# Neato_Laser_USB.net
KiCad netlist of a schematic drawn in EAGLE
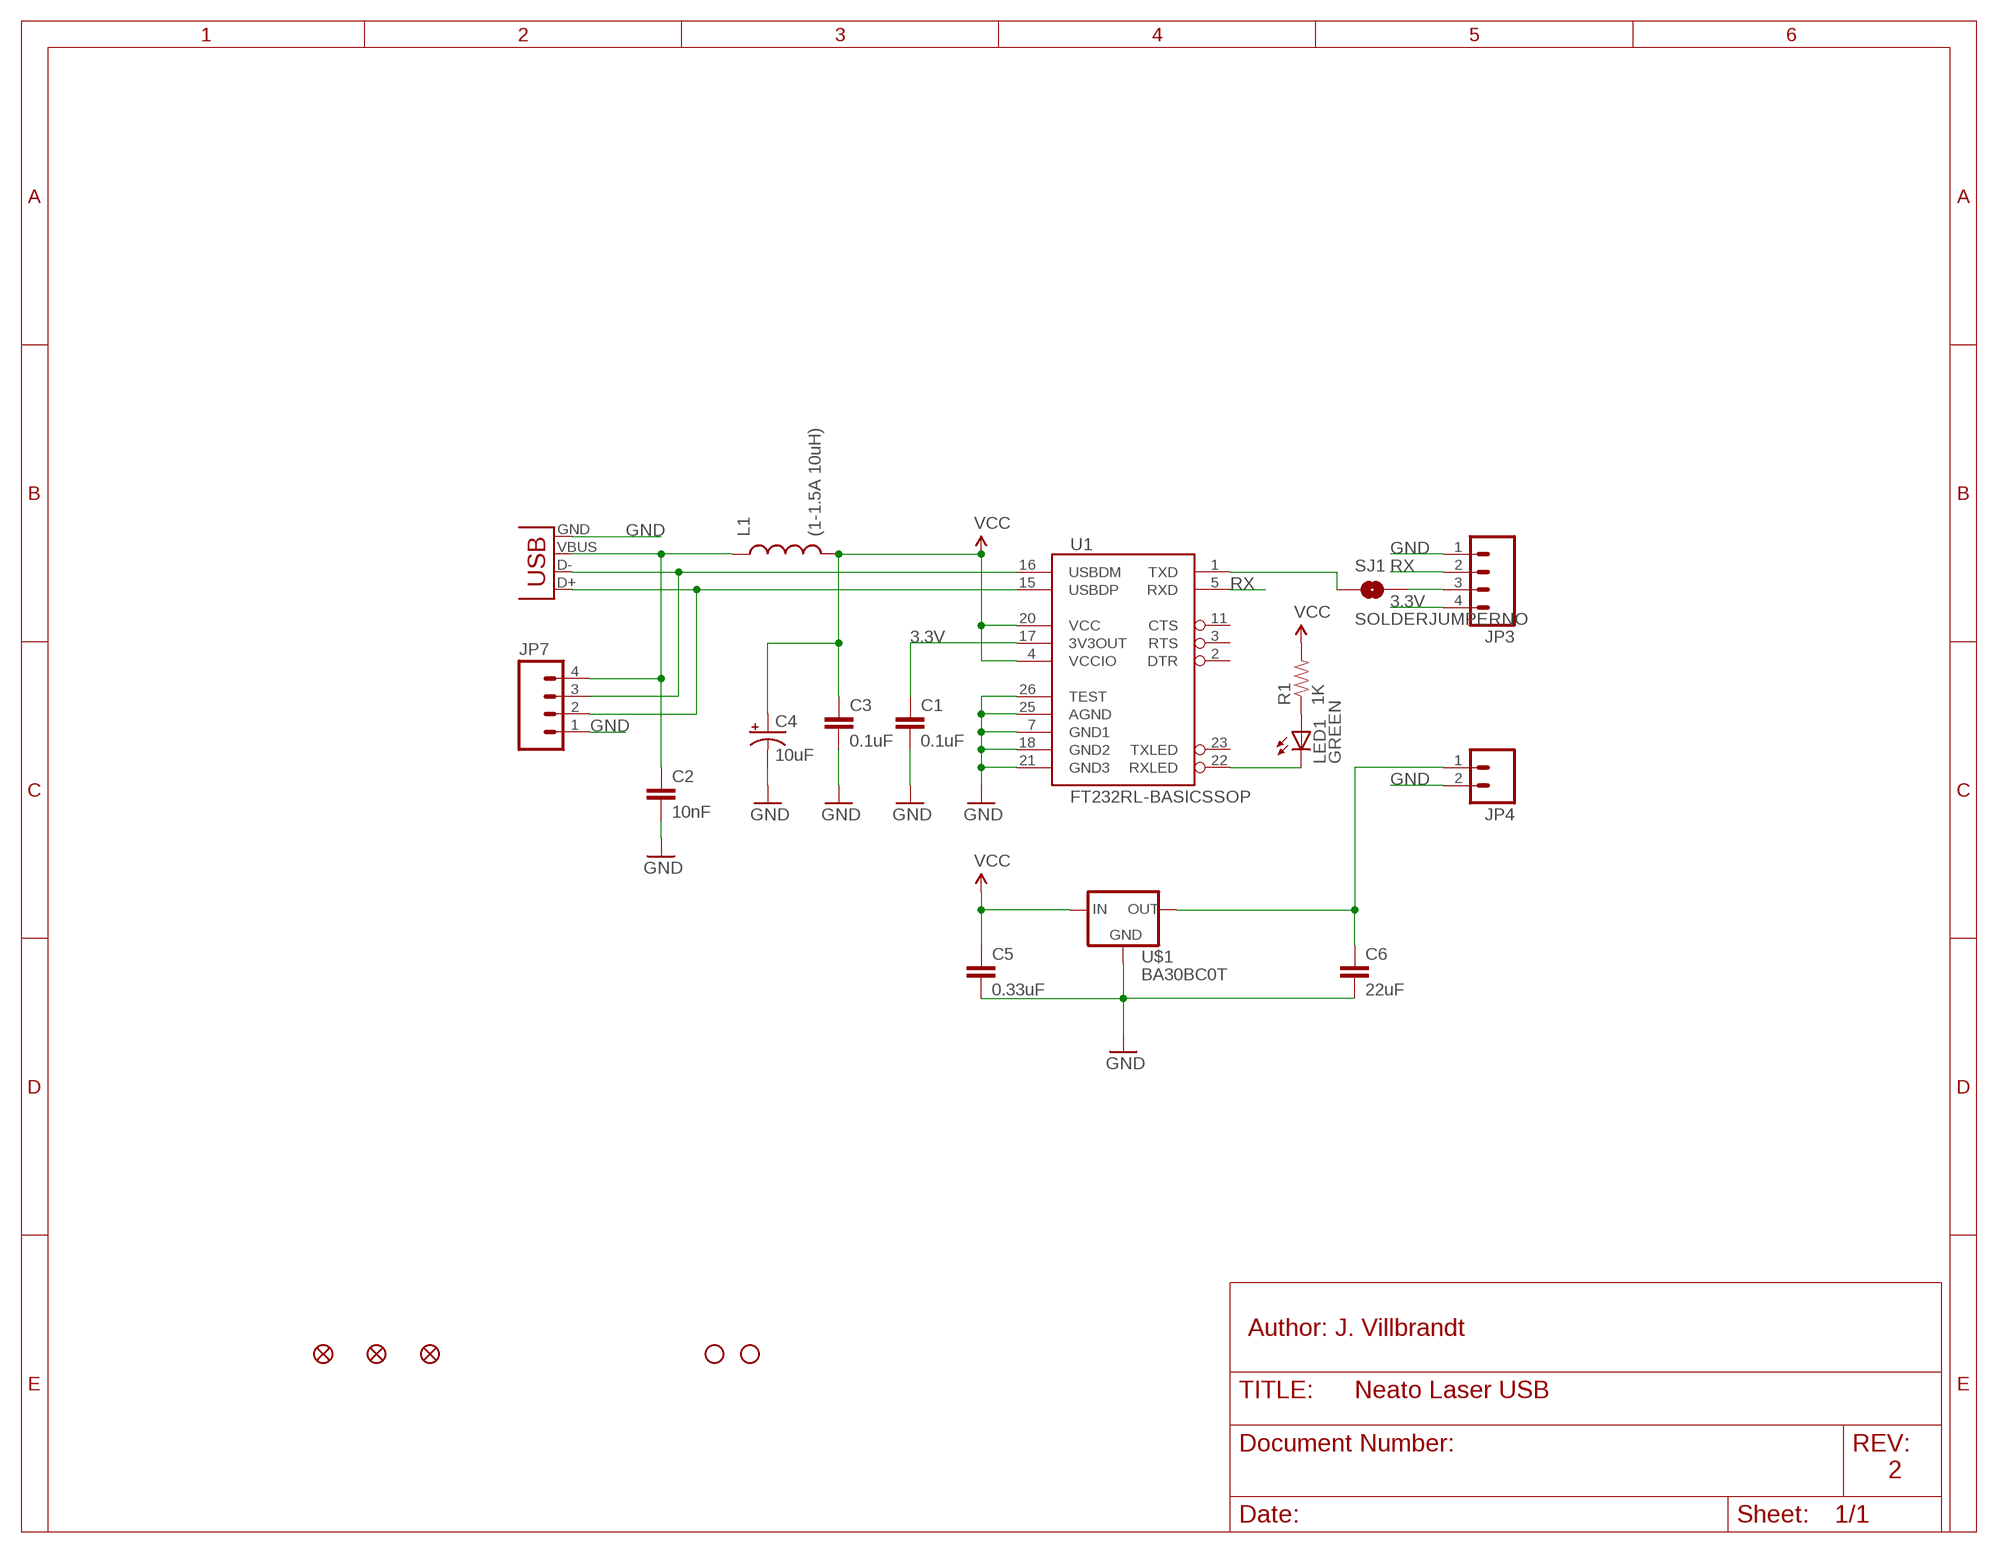
[diagram p0: schematic, sheet 1]

(export (version "E")
  (design (tool "Eeschema 10.0.6"))
  (components
    (comp (ref "C1")
      (value "0.1uF")
      (footprint "eagle-import:0603-CAP")
      (libsource (lib "eagle-import") (part "CAP0603-CAP"))
    )
    (comp (ref "C2")
      (value "10nF")
      (footprint "eagle-import:0603-CAP")
      (libsource (lib "eagle-import") (part "CAP0603-CAP"))
    )
    (comp (ref "C3")
      (value "0.1uF")
      (footprint "eagle-import:0603-CAP")
      (libsource (lib "eagle-import") (part "CAP0603-CAP"))
    )
    (comp (ref "C4")
      (value "10uF")
      (footprint "eagle-import:EIA3216")
      (libsource (lib "eagle-import") (part "CAP_POL1206"))
    )
    (comp (ref "C5")
      (value "0.33uF")
      (footprint "eagle-import:0603-CAP")
      (libsource (lib "eagle-import") (part "CAP0603-CAP"))
    )
    (comp (ref "C6")
      (value "22uF")
      (footprint "eagle-import:0603-CAP")
      (libsource (lib "eagle-import") (part "CAP0603-CAP"))
    )
    (comp (ref "JP1")
      (value "STAND-OFF")
      (footprint "eagle-import:STAND-OFF")
      (libsource (lib "eagle-import") (part "STAND-OFF"))
    )
    (comp (ref "JP2")
      (value "STAND-OFF")
      (footprint "eagle-import:STAND-OFF")
      (libsource (lib "eagle-import") (part "STAND-OFF"))
    )
    (comp (ref "JP3")
      (value "M04JST-PTH")
      (footprint "eagle-import:JST-4-PTH")
      (libsource (lib "eagle-import") (part "M04JST-PTH"))
    )
    (comp (ref "JP4")
      (value "M02JST-PTH-2")
      (footprint "eagle-import:JST-2-PTH")
      (libsource (lib "eagle-import") (part "M02JST-PTH-2"))
    )
    (comp (ref "JP5")
      (value "FIDUCIAL1X2.5")
      (footprint "eagle-import:FIDUCIAL-1X2.5")
      (libsource (lib "eagle-import") (part "FIDUCIAL1X2.5"))
    )
    (comp (ref "JP6")
      (value "FIDUCIAL1X2.5")
      (footprint "eagle-import:FIDUCIAL-1X2.5")
      (libsource (lib "eagle-import") (part "FIDUCIAL1X2.5"))
    )
    (comp (ref "JP7")
      (value "M04PTH")
      (footprint "eagle-import:1X04")
      (libsource (lib "eagle-import") (part "M04PTH"))
    )
    (comp (ref "JP8")
      (value "FIDUCIAL1X2.5")
      (footprint "eagle-import:FIDUCIAL-1X2.5")
      (libsource (lib "eagle-import") (part "FIDUCIAL1X2.5"))
    )
    (comp (ref "L1")
      (value "(1-1.5A 10uH)")
      (footprint "eagle-import:0603")
      (libsource (lib "eagle-import") (part "INDUCTOR0603"))
    )
    (comp (ref "LED1")
      (value "GREEN")
      (footprint "eagle-import:LED-0603")
      (libsource (lib "eagle-import") (part "LED0603"))
    )
    (comp (ref "R1")
      (value "1K")
      (footprint "eagle-import:0402-RES")
      (libsource (lib "eagle-import") (part "RESISTOR0402-RES"))
    )
    (comp (ref "SJ1")
      (value "SOLDERJUMPERNO")
      (footprint "eagle-import:SJ_2S-NO")
      (libsource (lib "eagle-import") (part "SOLDERJUMPERNO"))
    )
    (comp (ref "U$1")
      (value "BA30BC0T")
      (footprint "eagle-import:78XXL")
      (libsource (lib "eagle-import") (part "BA15BC0WT"))
    )
    (comp (ref "U1")
      (value "FT232RL-BASICSSOP")
      (footprint "eagle-import:SSOP28DB")
      (libsource (lib "eagle-import") (part "FT232RL-BASICSSOP"))
    )
    (comp (ref "X1")
      (value "USBSMD")
      (footprint "eagle-import:USB-MINIB")
      (libsource (lib "eagle-import") (part "USBSMD"))
    )
  )
  (nets
    (net (code "1") (name "/3.3V") (class "Default")
      (node (ref "C1") (pin "1") (pinfunction "1_1") (pintype "passive"))
      (node (ref "JP3") (pin "4") (pinfunction "4_4") (pintype "passive"))
      (node (ref "U1") (pin "17") (pinfunction "3V3OUT_17") (pintype "output"))
    )
    (net (code "2") (name "/RX") (class "Default")
      (node (ref "JP3") (pin "2") (pinfunction "2_2") (pintype "passive"))
      (node (ref "U1") (pin "5") (pinfunction "RXD_5") (pintype "input"))
    )
    (net (code "3") (name "GND") (class "Default")
      (node (ref "C1") (pin "2") (pinfunction "2_2") (pintype "passive"))
      (node (ref "C2") (pin "2") (pinfunction "2_2") (pintype "passive"))
      (node (ref "C3") (pin "2") (pinfunction "2_2") (pintype "passive"))
      (node (ref "C4") (pin "C") (pinfunction "-_C") (pintype "passive"))
      (node (ref "C5") (pin "2") (pinfunction "2_2") (pintype "passive"))
      (node (ref "C6") (pin "2") (pinfunction "2_2") (pintype "passive"))
      (node (ref "JP3") (pin "1") (pinfunction "1_1") (pintype "passive"))
      (node (ref "JP4") (pin "2") (pinfunction "2_2") (pintype "passive"))
      (node (ref "JP7") (pin "1") (pinfunction "1_1") (pintype "passive"))
      (node (ref "U$1") (pin "GND") (pinfunction "GND_GND") (pintype "input"))
      (node (ref "U1") (pin "18") (pinfunction "GND2_18") (pintype "power_in"))
      (node (ref "U1") (pin "21") (pinfunction "GND3_21") (pintype "power_in"))
      (node (ref "U1") (pin "25") (pinfunction "AGND_25") (pintype "power_in"))
      (node (ref "U1") (pin "26") (pinfunction "TEST_26") (pintype "input"))
      (node (ref "U1") (pin "7") (pinfunction "GND1_7") (pintype "power_in"))
      (node (ref "X1") (pin "GND") (pinfunction "GND_GND") (pintype "bidirectional"))
    )
    (net (code "4") (name "Net-(C2-Pad1)") (class "Default")
      (node (ref "C2") (pin "1") (pinfunction "1_1") (pintype "passive"))
      (node (ref "JP7") (pin "4") (pinfunction "4_4") (pintype "passive"))
      (node (ref "L1") (pin "1") (pinfunction "1_1") (pintype "passive"))
      (node (ref "X1") (pin "VBUS") (pinfunction "VBUS_VBUS") (pintype "bidirectional"))
    )
    (net (code "5") (name "Net-(C6-Pad1)") (class "Default")
      (node (ref "C6") (pin "1") (pinfunction "1_1") (pintype "passive"))
      (node (ref "JP4") (pin "1") (pinfunction "1_1") (pintype "passive"))
      (node (ref "U$1") (pin "OUT") (pinfunction "OUT_OUT") (pintype "output"))
    )
    (net (code "6") (name "Net-(JP3-Pad3)") (class "Default")
      (node (ref "JP3") (pin "3") (pinfunction "3_3") (pintype "passive"))
      (node (ref "SJ1") (pin "2") (pinfunction "2_2") (pintype "passive"))
    )
    (net (code "7") (name "Net-(LED1-PadA)") (class "Default")
      (node (ref "LED1") (pin "A") (pinfunction "A_A") (pintype "passive"))
      (node (ref "R1") (pin "1") (pinfunction "1_1") (pintype "passive"))
    )
    (net (code "8") (name "Net-(U1-RXLED)") (class "Default")
      (node (ref "LED1") (pin "C") (pinfunction "C_C") (pintype "passive"))
      (node (ref "U1") (pin "22") (pinfunction "RXLED_22") (pintype "bidirectional"))
    )
    (net (code "9") (name "Net-(U1-TXD)") (class "Default")
      (node (ref "SJ1") (pin "1") (pinfunction "1_1") (pintype "passive"))
      (node (ref "U1") (pin "1") (pinfunction "TXD_1") (pintype "output"))
    )
    (net (code "10") (name "Net-(U1-USBDM)") (class "Default")
      (node (ref "JP7") (pin "3") (pinfunction "3_3") (pintype "passive"))
      (node (ref "U1") (pin "16") (pinfunction "USBDM_16") (pintype "bidirectional"))
      (node (ref "X1") (pin "D-") (pinfunction "D-_D-") (pintype "bidirectional"))
    )
    (net (code "11") (name "Net-(U1-USBDP)") (class "Default")
      (node (ref "JP7") (pin "2") (pinfunction "2_2") (pintype "passive"))
      (node (ref "U1") (pin "15") (pinfunction "USBDP_15") (pintype "bidirectional"))
      (node (ref "X1") (pin "D+") (pinfunction "D+_D+") (pintype "bidirectional"))
    )
    (net (code "12") (name "VCC") (class "Default")
      (node (ref "C3") (pin "1") (pinfunction "1_1") (pintype "passive"))
      (node (ref "C4") (pin "A") (pinfunction "+_A") (pintype "passive"))
      (node (ref "C5") (pin "1") (pinfunction "1_1") (pintype "passive"))
      (node (ref "L1") (pin "2") (pinfunction "2_2") (pintype "passive"))
      (node (ref "R1") (pin "2") (pinfunction "2_2") (pintype "passive"))
      (node (ref "U$1") (pin "IN") (pinfunction "IN_IN") (pintype "input"))
      (node (ref "U1") (pin "20") (pinfunction "VCC_20") (pintype "power_in"))
      (node (ref "U1") (pin "4") (pinfunction "VCCIO_4") (pintype "power_in"))
    )
    (net (code "13") (name "unconnected-(U1-CTS-Pad11)") (class "Default")
      (node (ref "U1") (pin "11") (pinfunction "CTS_11") (pintype "bidirectional"))
    )
    (net (code "14") (name "unconnected-(U1-DTR-Pad2)") (class "Default")
      (node (ref "U1") (pin "2") (pinfunction "DTR_2") (pintype "bidirectional"))
    )
    (net (code "15") (name "unconnected-(U1-RTS-Pad3)") (class "Default")
      (node (ref "U1") (pin "3") (pinfunction "RTS_3") (pintype "bidirectional"))
    )
    (net (code "16") (name "unconnected-(U1-TXLED-Pad23)") (class "Default")
      (node (ref "U1") (pin "23") (pinfunction "TXLED_23") (pintype "bidirectional"))
    )
  )
)
